# Gas_Sampler-RFD_Radio.net
KiCad netlist of a schematic drawn in Altium Designer
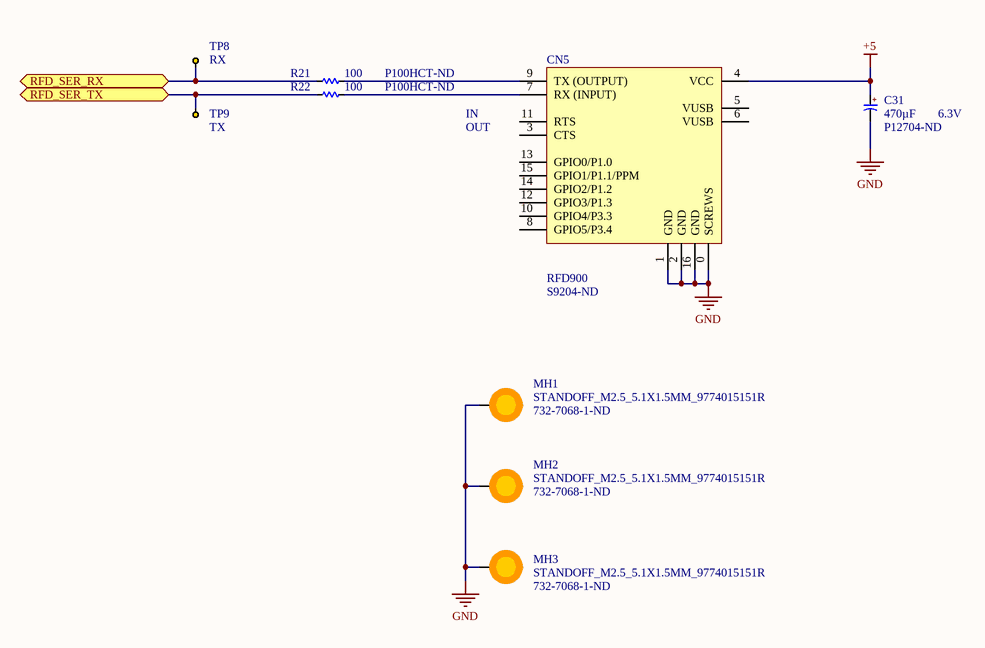
[diagram p0: Gas_Sampler-RFD_Radio.SchDoc]

(export (version "E")
  (design (tool "Eeschema 10.0.6"))
  (components
    (comp (ref "C31")
      (value "470µF")
      (footprint "CAP_RADIAL_8MM_DIA_11.5MM_LEN_3.5MM_LEADSPACE")
      (description "CAP ALUM 470UF 6.3V 20% RADIAL")
      (fields
        (field (name "MANUFACTURER") "Panasonic Electronic Components")
        (field (name "MANUFACTURER PART NUMBER") "EEU-FC0J471")
        (field (name "VOLTAGE - RATED") "6.3V")
        (field (name "SUPPLIER PART NUMBER 1") "P12704-ND")
      )
      (libsource (lib "capacitor") (part "CAP_ALUM_470UF_6.3V_20%_RADIAL_8X11.5MM"))
    )
    (comp (ref "CN5")
      (value "RFD900")
      (footprint "RFD900_FLAT")
      (fields
        (field (name "MANUFACTURER PART NUMBER") "SFH11-PBPC-D08-RA-BK")
        (field (name "MANUFACTURER") "Sullins Connector Solutions")
        (field (name "SUPPLIER PART NUMBER 1") "S9204-ND")
      )
      (libsource (lib "modules") (part "RFD900"))
    )
    (comp (ref "MH1")
      (value "STANDOFF_M2.5_5.1X1.5MM_9774015151R")
      (footprint "STANDOFF_M2.5_5.1X1.5MM")
      (description "RND STNDFF M2.5X0.45 STEEL 1.5MM")
      (fields
        (field (name "MANUFACTURER PART NUMBER") "9774015151R")
        (field (name "MANUFACTURER") "Wurth Electronics Inc.")
        (field (name "SUPPLIER PART NUMBER 1") "732-7068-1-ND")
      )
      (libsource (lib "mechanical") (part "STANDOFF_M2.5_5.1X1.5MM_9774015151R"))
    )
    (comp (ref "MH2")
      (value "STANDOFF_M2.5_5.1X1.5MM_9774015151R")
      (footprint "STANDOFF_M2.5_5.1X1.5MM")
      (description "RND STNDFF M2.5X0.45 STEEL 1.5MM")
      (fields
        (field (name "MANUFACTURER PART NUMBER") "9774015151R")
        (field (name "MANUFACTURER") "Wurth Electronics Inc.")
        (field (name "SUPPLIER PART NUMBER 1") "732-7068-1-ND")
      )
      (libsource (lib "mechanical") (part "STANDOFF_M2.5_5.1X1.5MM_9774015151R"))
    )
    (comp (ref "MH3")
      (value "STANDOFF_M2.5_5.1X1.5MM_9774015151R")
      (footprint "STANDOFF_M2.5_5.1X1.5MM")
      (description "RND STNDFF M2.5X0.45 STEEL 1.5MM")
      (fields
        (field (name "MANUFACTURER PART NUMBER") "9774015151R")
        (field (name "MANUFACTURER") "Wurth Electronics Inc.")
        (field (name "SUPPLIER PART NUMBER 1") "732-7068-1-ND")
      )
      (libsource (lib "mechanical") (part "STANDOFF_M2.5_5.1X1.5MM_9774015151R"))
    )
    (comp (ref "R21")
      (value "100")
      (footprint "R0603")
      (description "RES 100 OHM 1/10W 1% 0603 SMD")
      (fields
        (field (name "MANUFACTURER") "Panasonic Electronic Components")
        (field (name "MANUFACTURER PART NUMBER") "ERJ-3EKF1000V")
        (field (name "SUPPLIER PART NUMBER 1") "P100HCT-ND")
      )
      (libsource (lib "resistor") (part "RES_0603_100_OHM_1/10W_1%"))
    )
    (comp (ref "R22")
      (value "100")
      (footprint "R0603")
      (description "RES 100 OHM 1/10W 1% 0603 SMD")
      (fields
        (field (name "MANUFACTURER") "Panasonic Electronic Components")
        (field (name "MANUFACTURER PART NUMBER") "ERJ-3EKF1000V")
        (field (name "SUPPLIER PART NUMBER 1") "P100HCT-ND")
      )
      (libsource (lib "resistor") (part "RES_0603_100_OHM_1/10W_1%"))
    )
    (comp (ref "TP8")
      (value "RX")
      (footprint "TP_KEYSTONE_5001")
      (description "PC TEST POINT TH RING")
      (fields
        (field (name "MANUFACTURER") "Keystone Electronics")
        (field (name "MANUFACTURER PART NUMBER") "5001")
      )
      (libsource (lib "miscellaneous") (part "TEST_KEYSTONE5001"))
    )
    (comp (ref "TP9")
      (value "TX")
      (footprint "TP_KEYSTONE_5001")
      (description "PC TEST POINT TH RING")
      (fields
        (field (name "MANUFACTURER") "Keystone Electronics")
        (field (name "MANUFACTURER PART NUMBER") "5001")
      )
      (libsource (lib "miscellaneous") (part "TEST_KEYSTONE5001"))
    )
  )
  (nets
    (net (code "1") (name "+5") (class "Default")
      (node (ref "C31") (pin "1") (pintype "passive"))
      (node (ref "CN5") (pin "4") (pinfunction "VCC_4") (pintype "passive"))
    )
    (net (code "2") (name "/RFD_SER_RX") (class "Default")
      (node (ref "R21") (pin "1") (pintype "passive"))
      (node (ref "TP8") (pin "1") (pintype "passive"))
    )
    (net (code "3") (name "/RFD_SER_TX") (class "Default")
      (node (ref "R22") (pin "1") (pintype "passive"))
      (node (ref "TP9") (pin "1") (pintype "passive"))
    )
    (net (code "4") (name "GND") (class "Default")
      (node (ref "C31") (pin "2") (pintype "passive"))
      (node (ref "CN5") (pin "0") (pinfunction "SCREWS_0") (pintype "passive"))
      (node (ref "CN5") (pin "1") (pinfunction "GND_1") (pintype "passive"))
      (node (ref "CN5") (pin "16") (pinfunction "GND_16") (pintype "passive"))
      (node (ref "CN5") (pin "2") (pinfunction "GND_2") (pintype "passive"))
      (node (ref "MH1") (pin "1") (pintype "passive"))
      (node (ref "MH2") (pin "1") (pintype "passive"))
      (node (ref "MH3") (pin "1") (pintype "passive"))
    )
    (net (code "5") (name "Net-(CN5-RX_(INPUT))") (class "Default")
      (node (ref "CN5") (pin "7") (pinfunction "RX_(INPUT)_7") (pintype "passive"))
      (node (ref "R22") (pin "2") (pintype "passive"))
    )
    (net (code "6") (name "Net-(CN5-TX_(OUTPUT))") (class "Default")
      (node (ref "CN5") (pin "9") (pinfunction "TX_(OUTPUT)_9") (pintype "passive"))
      (node (ref "R21") (pin "2") (pintype "passive"))
    )
    (net (code "7") (name "unconnected-(CN5-CTS-Pad3)") (class "Default")
      (node (ref "CN5") (pin "3") (pinfunction "CTS_3") (pintype "passive"))
    )
    (net (code "8") (name "unconnected-(CN5-GPIO0{slash}P1.0-Pad13)") (class "Default")
      (node (ref "CN5") (pin "13") (pinfunction "GPIO0/P1.0_13") (pintype "passive"))
    )
    (net (code "9") (name "unconnected-(CN5-GPIO1{slash}P1.1{slash}PPM-Pad15)") (class "Default")
      (node (ref "CN5") (pin "15") (pinfunction "GPIO1/P1.1/PPM_15") (pintype "passive"))
    )
    (net (code "10") (name "unconnected-(CN5-GPIO2{slash}P1.2-Pad14)") (class "Default")
      (node (ref "CN5") (pin "14") (pinfunction "GPIO2/P1.2_14") (pintype "passive"))
    )
    (net (code "11") (name "unconnected-(CN5-GPIO3{slash}P1.3-Pad12)") (class "Default")
      (node (ref "CN5") (pin "12") (pinfunction "GPIO3/P1.3_12") (pintype "passive"))
    )
    (net (code "12") (name "unconnected-(CN5-GPIO4{slash}P3.3-Pad10)") (class "Default")
      (node (ref "CN5") (pin "10") (pinfunction "GPIO4/P3.3_10") (pintype "passive"))
    )
    (net (code "13") (name "unconnected-(CN5-GPIO5{slash}P3.4-Pad8)") (class "Default")
      (node (ref "CN5") (pin "8") (pinfunction "GPIO5/P3.4_8") (pintype "passive"))
    )
    (net (code "14") (name "unconnected-(CN5-RTS-Pad11)") (class "Default")
      (node (ref "CN5") (pin "11") (pinfunction "RTS_11") (pintype "passive"))
    )
    (net (code "15") (name "unconnected-(CN5-VUSB-Pad5)") (class "Default")
      (node (ref "CN5") (pin "5") (pinfunction "VUSB_5") (pintype "passive"))
    )
    (net (code "16") (name "unconnected-(CN5-VUSB-Pad6)") (class "Default")
      (node (ref "CN5") (pin "6") (pinfunction "VUSB_6") (pintype "passive"))
    )
  )
)
